# Micromirror_Ampli_PCB.net
KiCad netlist of a schematic drawn in EAGLE
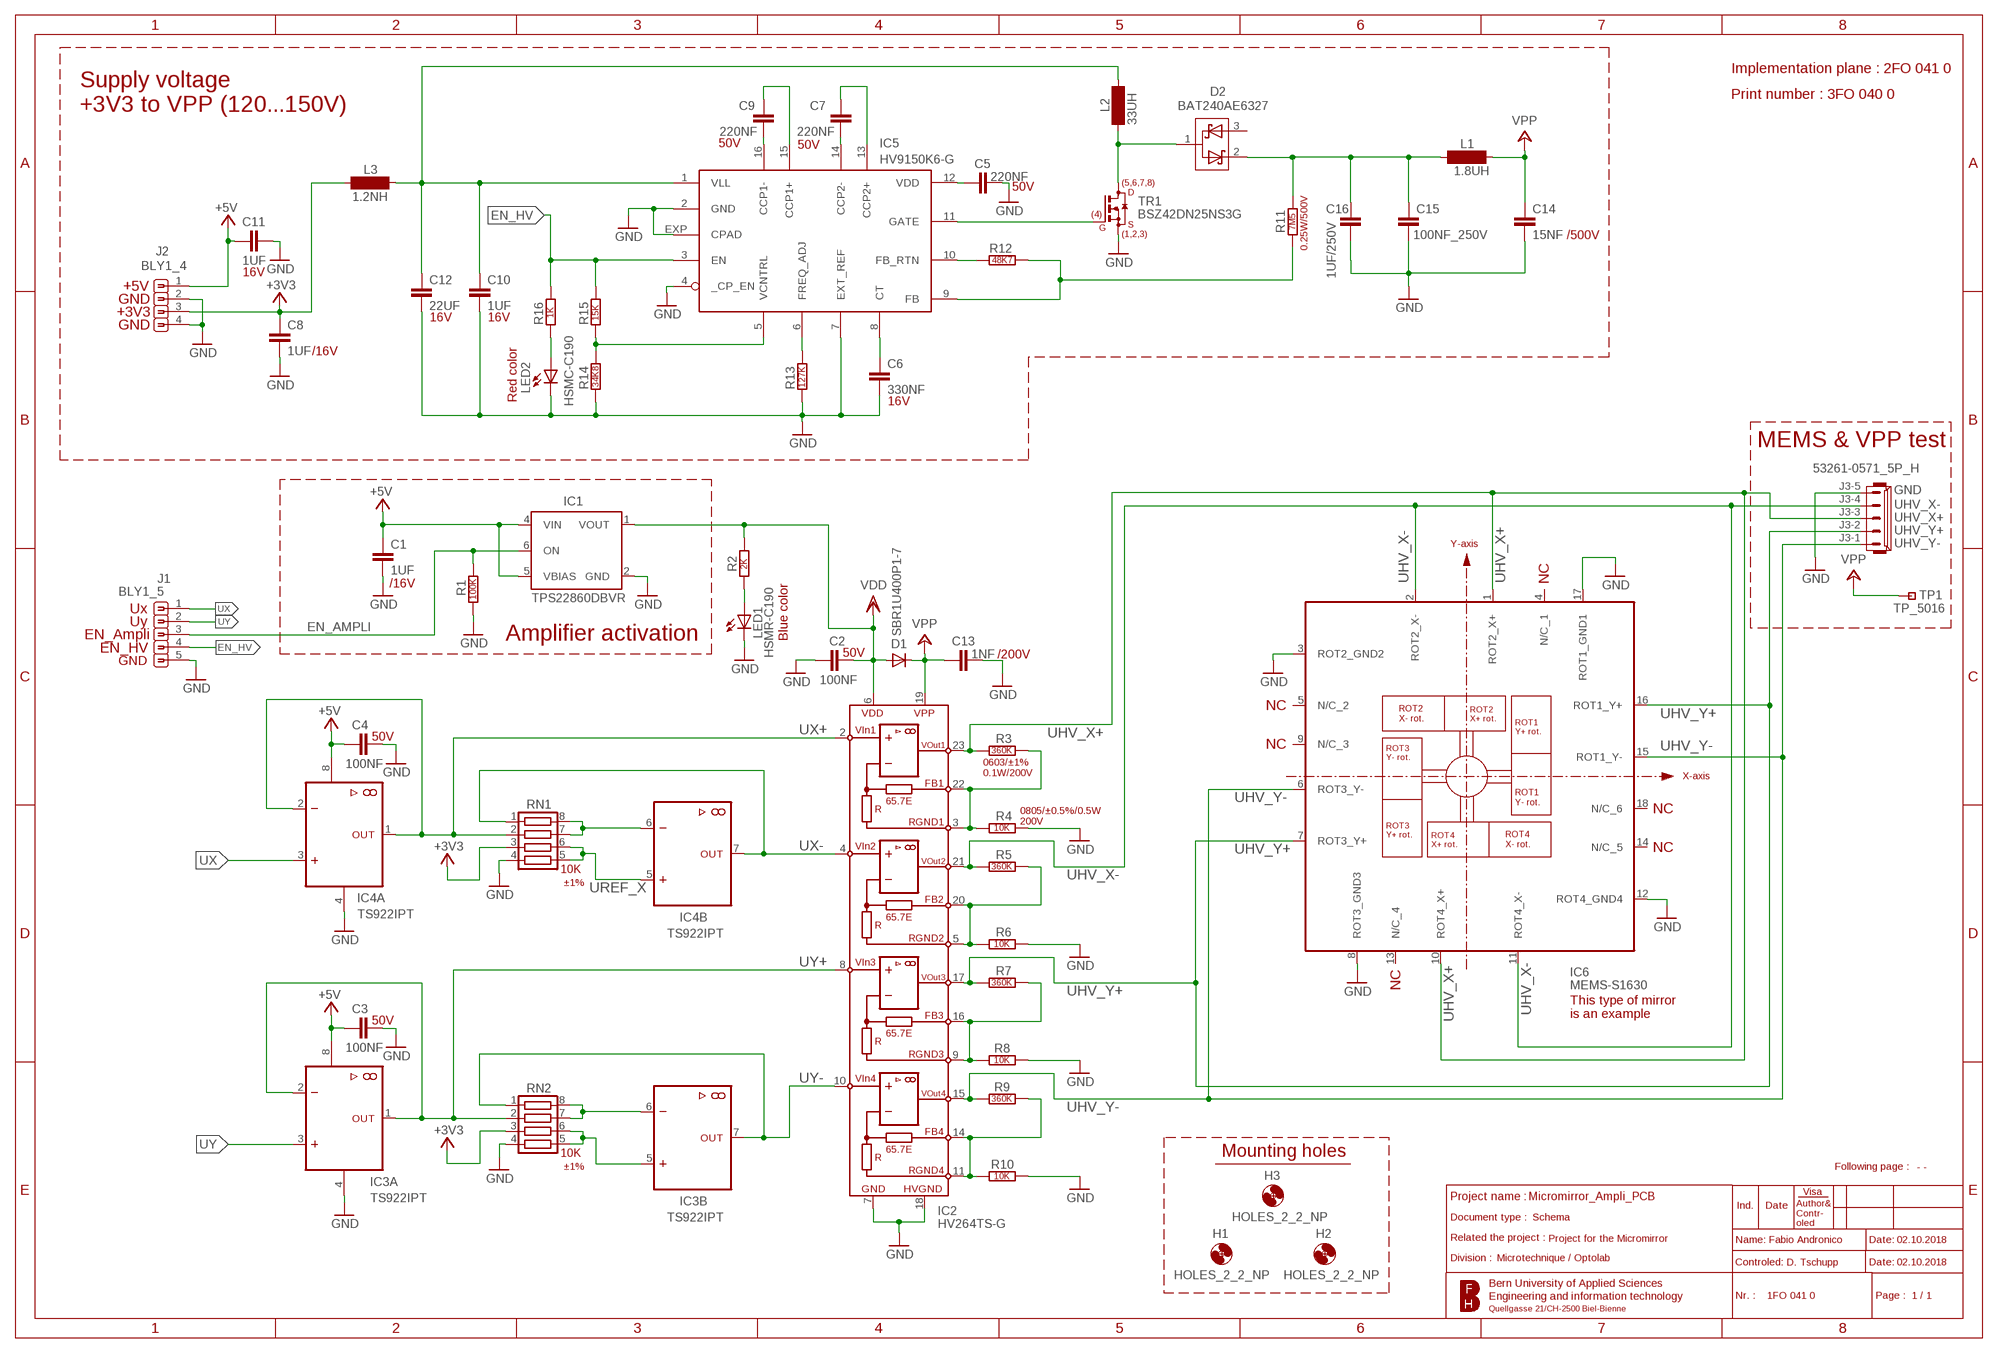
[diagram p0: schematic, sheet 1]

(export (version "E")
  (design (tool "Eeschema 10.0.6"))
  (components
    (comp (ref "C1")
      (value "1UF")
      (footprint "eagle-import:C0603")
      (fields (field (name "MANUFACTURER") "KEMET") (field (name "TOLERANCE") "±5%"))
      (libsource (lib "eagle-import") (part "1UF"))
    )
    (comp (ref "C2")
      (value "100NF")
      (footprint "eagle-import:C0603")
      (fields (field (name "MANUFACTURER") "Kemet") (field (name "TOLERANCE") "±10%"))
      (libsource (lib "eagle-import") (part "100NF"))
    )
    (comp (ref "C3")
      (value "100NF")
      (footprint "eagle-import:C0603")
      (fields (field (name "MANUFACTURER") "Kemet") (field (name "TOLERANCE") "±10%"))
      (libsource (lib "eagle-import") (part "100NF"))
    )
    (comp (ref "C4")
      (value "100NF")
      (footprint "eagle-import:C0603")
      (fields (field (name "MANUFACTURER") "Kemet") (field (name "TOLERANCE") "±10%"))
      (libsource (lib "eagle-import") (part "100NF"))
    )
    (comp (ref "C5")
      (value "220NF")
      (footprint "eagle-import:C0603")
      (fields (field (name "MANUFACTURER") "Murata") (field (name "TOLERANCE") "±10%"))
      (libsource (lib "eagle-import") (part "220NF"))
    )
    (comp (ref "C6")
      (value "330NF")
      (footprint "eagle-import:C0603")
      (fields (field (name "MANUFACTURER") "AVX") (field (name "TOLERANCE") "±10%"))
      (libsource (lib "eagle-import") (part "330NF"))
    )
    (comp (ref "C7")
      (value "220NF")
      (footprint "eagle-import:C0603")
      (fields (field (name "MANUFACTURER") "Murata") (field (name "TOLERANCE") "±10%"))
      (libsource (lib "eagle-import") (part "220NF"))
    )
    (comp (ref "C8")
      (value "1UF")
      (footprint "eagle-import:C0603")
      (fields (field (name "MANUFACTURER") "KEMET") (field (name "TOLERANCE") "±5%"))
      (libsource (lib "eagle-import") (part "1UF"))
    )
    (comp (ref "C9")
      (value "220NF")
      (footprint "eagle-import:C0603")
      (fields (field (name "MANUFACTURER") "Murata") (field (name "TOLERANCE") "±10%"))
      (libsource (lib "eagle-import") (part "220NF"))
    )
    (comp (ref "C10")
      (value "1UF")
      (footprint "eagle-import:C0603")
      (fields (field (name "MANUFACTURER") "KEMET") (field (name "TOLERANCE") "±5%"))
      (libsource (lib "eagle-import") (part "1UF"))
    )
    (comp (ref "C11")
      (value "1UF")
      (footprint "eagle-import:C0603")
      (fields (field (name "MANUFACTURER") "KEMET") (field (name "TOLERANCE") "±5%"))
      (libsource (lib "eagle-import") (part "1UF"))
    )
    (comp (ref "C12")
      (value "22UF")
      (footprint "eagle-import:C0805")
      (fields (field (name "MANUFACTURER") "Murata") (field (name "TOLERANCE") "±20%"))
      (libsource (lib "eagle-import") (part "22UF"))
    )
    (comp (ref "C13")
      (value "1NF")
      (footprint "eagle-import:C0603")
      (fields (field (name "MANUFACTURER") "Kemet") (field (name "TOLERANCE") "±5%"))
      (libsource (lib "eagle-import") (part "1NF"))
    )
    (comp (ref "C14")
      (value "15NF")
      (footprint "eagle-import:C0805")
      (fields (field (name "MANUFACTURER") "Kemet") (field (name "TOLERANCE") "±5%"))
      (libsource (lib "eagle-import") (part "15NF"))
    )
    (comp (ref "C15")
      (value "100NF_250V")
      (footprint "eagle-import:C0805")
      (fields (field (name "MANUFACTURER") "TDK") (field (name "TOLERANCE") "±20%"))
      (libsource (lib "eagle-import") (part "100NF_250V"))
    )
    (comp (ref "C16")
      (value "1UF/250V")
      (footprint "eagle-import:C1812")
      (fields (field (name "MANUFACTURER") "TDK") (field (name "TOLERANCE") "±10%"))
      (libsource (lib "eagle-import") (part "1UF/250V"))
    )
    (comp (ref "D1")
      (value "SBR1U400P1-7")
      (footprint "eagle-import:POWERDI_123")
      (libsource (lib "eagle-import") (part "SBR1U400P1-7"))
    )
    (comp (ref "D2")
      (value "BAT240AE6327")
      (footprint "eagle-import:SOT23-3")
      (fields (field (name "MANUFACTURER") "Infineon"))
      (libsource (lib "eagle-import") (part "BAT240AE6327"))
    )
    (comp (ref "H1")
      (value "HOLES_2_2_NP")
      (footprint "eagle-import:2_2_NP")
      (libsource (lib "eagle-import") (part "HOLES_2_2_NP"))
    )
    (comp (ref "H2")
      (value "HOLES_2_2_NP")
      (footprint "eagle-import:2_2_NP")
      (libsource (lib "eagle-import") (part "HOLES_2_2_NP"))
    )
    (comp (ref "H3")
      (value "HOLES_2_2_NP")
      (footprint "eagle-import:2_2_NP")
      (libsource (lib "eagle-import") (part "HOLES_2_2_NP"))
    )
    (comp (ref "IC1")
      (value "TPS22860DBVR")
      (footprint "eagle-import:SOT23-6")
      (fields (field (name "MANUFACTURER") "Texas Instruments"))
      (libsource (lib "eagle-import") (part "TPS22860DBVR"))
    )
    (comp (ref "IC2")
      (value "HV264TS-G")
      (footprint "eagle-import:TSSOP24")
      (fields (field (name "MANUFACTURER") "Supertex"))
      (libsource (lib "eagle-import") (part "HV264TS-G"))
    )
    (comp (ref "IC3")
      (value "TS922IPT")
      (footprint "eagle-import:TSSOP8")
      (libsource (lib "eagle-import") (part "TS922IPT"))
    )
    (comp (ref "IC4")
      (value "TS922IPT")
      (footprint "eagle-import:TSSOP8")
      (libsource (lib "eagle-import") (part "TS922IPT"))
    )
    (comp (ref "IC5")
      (value "HV9150K6-G")
      (footprint "eagle-import:QFN16")
      (fields (field (name "MANUFACTURER") "Microchip"))
      (libsource (lib "eagle-import") (part "HV9150K6-G"))
    )
    (comp (ref "IC6")
      (value "MEMS-S1630")
      (footprint "eagle-import:LCC18")
      (fields (field (name "MANUFACTURER") "mirrorcletech"))
      (libsource (lib "eagle-import") (part "MEMS-S1630"))
    )
    (comp (ref "J1")
      (value "BLY1_5")
      (footprint "eagle-import:BLY1_5_2MM")
      (fields (field (name "MANUFACTURER") "Fischer Elektronik"))
      (libsource (lib "eagle-import") (part "BLY1_5"))
    )
    (comp (ref "J2")
      (value "BLY1_4")
      (footprint "eagle-import:BLY1_4_2MM")
      (fields (field (name "MANUFACTURER") "Fischer Elektronik"))
      (libsource (lib "eagle-import") (part "BLY1_4"))
    )
    (comp (ref "J3")
      (value "53261-0571_5P_H")
      (footprint "eagle-import:53261-05")
      (fields (field (name "MANUFACTURER") "Molex"))
      (libsource (lib "eagle-import") (part "53261-0571_5P_H"))
    )
    (comp (ref "L1")
      (value "1.8UH")
      (footprint "eagle-import:L0805")
      (fields (field (name "MANUFACTURER") "Laird"))
      (libsource (lib "eagle-import") (part "1.8UH"))
    )
    (comp (ref "L2")
      (value "33UH")
      (footprint "eagle-import:NR5040")
      (fields (field (name "MANUFACTURER") "Taiyo Yuden") (field (name "TOLERANCE") "±20%"))
      (libsource (lib "eagle-import") (part "33UH"))
    )
    (comp (ref "L3")
      (value "1.2NH")
      (footprint "eagle-import:L08051R2CEWTR")
      (fields (field (name "MANUFACTURER") "AVX") (field (name "TOLERANCE") "±16%"))
      (libsource (lib "eagle-import") (part "1.2NH"))
    )
    (comp (ref "LED1")
      (value "HSMR-C190")
      (footprint "eagle-import:CHIP-LED-0603")
      (fields (field (name "MANUFACTURER") "Broadcom Limited"))
      (libsource (lib "eagle-import") (part "HSMR-C190"))
    )
    (comp (ref "LED2")
      (value "HSMC-C190")
      (footprint "eagle-import:CHIP-LED-0603")
      (fields (field (name "MANUFACTURER") "Broadcom Limited"))
      (libsource (lib "eagle-import") (part "HSMC-C190"))
    )
    (comp (ref "R1")
      (value "100K")
      (footprint "eagle-import:R0603")
      (fields
        (field (name "MANUFACTURER") "KOA")
        (field (name "POWER") "0,1W")
        (field (name "TOLERANCE") "±1%")
      )
      (libsource (lib "eagle-import") (part "100K"))
    )
    (comp (ref "R2")
      (value "2K")
      (footprint "eagle-import:R0603")
      (fields
        (field (name "MANUFACTURER") "KOA")
        (field (name "POWER") "0,1W")
        (field (name "TOLERANCE") "±1%")
      )
      (libsource (lib "eagle-import") (part "2K"))
    )
    (comp (ref "R3")
      (value "360K")
      (footprint "eagle-import:R0603")
      (fields
        (field (name "MANUFACTURER") "Multicomp")
        (field (name "POWER") "0,1W")
        (field (name "TOLERANCE") "±1%")
      )
      (libsource (lib "eagle-import") (part "360K"))
    )
    (comp (ref "R4")
      (value "10K_0.5%")
      (footprint "eagle-import:R0805")
      (fields
        (field (name "MANUFACTURER") "KOA")
        (field (name "POWER") "0.5W")
        (field (name "TOLERANCE") "±0.5%")
      )
      (libsource (lib "eagle-import") (part "10K_0.5%"))
    )
    (comp (ref "R5")
      (value "360K")
      (footprint "eagle-import:R0603")
      (fields
        (field (name "MANUFACTURER") "Multicomp")
        (field (name "POWER") "0,1W")
        (field (name "TOLERANCE") "±1%")
      )
      (libsource (lib "eagle-import") (part "360K"))
    )
    (comp (ref "R6")
      (value "10K_0.5%")
      (footprint "eagle-import:R0805")
      (fields
        (field (name "MANUFACTURER") "KOA")
        (field (name "POWER") "0.5W")
        (field (name "TOLERANCE") "±0.5%")
      )
      (libsource (lib "eagle-import") (part "10K_0.5%"))
    )
    (comp (ref "R7")
      (value "360K")
      (footprint "eagle-import:R0603")
      (fields
        (field (name "MANUFACTURER") "Multicomp")
        (field (name "POWER") "0,1W")
        (field (name "TOLERANCE") "±1%")
      )
      (libsource (lib "eagle-import") (part "360K"))
    )
    (comp (ref "R8")
      (value "10K_0.5%")
      (footprint "eagle-import:R0805")
      (fields
        (field (name "MANUFACTURER") "KOA")
        (field (name "POWER") "0.5W")
        (field (name "TOLERANCE") "±0.5%")
      )
      (libsource (lib "eagle-import") (part "10K_0.5%"))
    )
    (comp (ref "R9")
      (value "360K")
      (footprint "eagle-import:R0603")
      (fields
        (field (name "MANUFACTURER") "Multicomp")
        (field (name "POWER") "0,1W")
        (field (name "TOLERANCE") "±1%")
      )
      (libsource (lib "eagle-import") (part "360K"))
    )
    (comp (ref "R10")
      (value "10K_0.5%")
      (footprint "eagle-import:R0805")
      (fields
        (field (name "MANUFACTURER") "KOA")
        (field (name "POWER") "0.5W")
        (field (name "TOLERANCE") "±0.5%")
      )
      (libsource (lib "eagle-import") (part "10K_0.5%"))
    )
    (comp (ref "R11")
      (value "7M5")
      (footprint "eagle-import:R1206")
      (fields
        (field (name "MANUFACTURER") "KOA")
        (field (name "POWER") "0,25W")
        (field (name "TOLERANCE") "±1%")
      )
      (libsource (lib "eagle-import") (part "7M5"))
    )
    (comp (ref "R12")
      (value "48K7")
      (footprint "eagle-import:R0603")
      (fields
        (field (name "MANUFACTURER") "Panasonic")
        (field (name "POWER") "0,1W")
        (field (name "TOLERANCE") "±1%")
      )
      (libsource (lib "eagle-import") (part "48K7"))
    )
    (comp (ref "R13")
      (value "127K")
      (footprint "eagle-import:R0603")
      (fields
        (field (name "MANUFACTURER") "Yageo")
        (field (name "POWER") "0,1W")
        (field (name "TOLERANCE") "±1%")
      )
      (libsource (lib "eagle-import") (part "127K"))
    )
    (comp (ref "R14")
      (value "34K8")
      (footprint "eagle-import:R0603")
      (fields
        (field (name "MANUFACTURER") "Panasonic")
        (field (name "POWER") "0,1W")
        (field (name "TOLERANCE") "±1%")
      )
      (libsource (lib "eagle-import") (part "34K8"))
    )
    (comp (ref "R15")
      (value "15K")
      (footprint "eagle-import:R0603")
      (fields
        (field (name "MANUFACTURER") "Panasonic")
        (field (name "POWER") "0,2W")
        (field (name "TOLERANCE") "±0.1%")
      )
      (libsource (lib "eagle-import") (part "15K"))
    )
    (comp (ref "R16")
      (value "1K_0.1W")
      (footprint "eagle-import:R0603")
      (fields
        (field (name "MANUFACTURER") "KOA")
        (field (name "POWER") "0,1W")
        (field (name "TOLERANCE") "±1%")
      )
      (libsource (lib "eagle-import") (part "1K_0.1W"))
    )
    (comp (ref "RN1")
      (value "10K")
      (footprint "eagle-import:RN1206")
      (fields (field (name "MANUFACTURER") "Bourns") (field (name "TOLERANCE") "±1%"))
      (libsource (lib "eagle-import") (part "10K"))
    )
    (comp (ref "RN2")
      (value "10K")
      (footprint "eagle-import:RN1206")
      (fields (field (name "MANUFACTURER") "Bourns") (field (name "TOLERANCE") "±1%"))
      (libsource (lib "eagle-import") (part "10K"))
    )
    (comp (ref "TP1")
      (value "TP_5016")
      (footprint "eagle-import:5016")
      (libsource (lib "eagle-import") (part "5016"))
    )
    (comp (ref "TR1")
      (value "BSZ42DN25NS3G")
      (footprint "eagle-import:TSDSON-8")
      (fields (field (name "MANUFACTURER") "Infineon"))
      (libsource (lib "eagle-import") (part "BSZ42DN25NS3G"))
    )
  )
  (nets
    (net (code "1") (name "+3V3") (class "Default")
      (node (ref "C8") (pin "1") (pinfunction "1_1") (pintype "passive"))
      (node (ref "J2") (pin "3") (pinfunction "3_3") (pintype "passive"))
      (node (ref "L3") (pin "1") (pinfunction "1_1") (pintype "passive"))
      (node (ref "RN1") (pin "3") (pinfunction "3_3") (pintype "passive"))
      (node (ref "RN2") (pin "3") (pinfunction "3_3") (pintype "passive"))
    )
    (net (code "2") (name "+5V") (class "Default")
      (node (ref "C1") (pin "1") (pinfunction "1_1") (pintype "passive"))
      (node (ref "C11") (pin "1") (pinfunction "1_1") (pintype "passive"))
      (node (ref "C3") (pin "1") (pinfunction "1_1") (pintype "passive"))
      (node (ref "C4") (pin "1") (pinfunction "1_1") (pintype "passive"))
      (node (ref "IC1") (pin "4") (pinfunction "VIN_4") (pintype "input"))
      (node (ref "IC1") (pin "5") (pinfunction "VBIAS_5") (pintype "input"))
      (node (ref "IC3") (pin "8") (pinfunction "+5V_8") (pintype "power_in"))
      (node (ref "IC4") (pin "8") (pinfunction "+5V_8") (pintype "power_in"))
      (node (ref "J2") (pin "1") (pinfunction "1_1") (pintype "passive"))
    )
    (net (code "3") (name "/EN_AMPLI") (class "Default")
      (node (ref "IC1") (pin "6") (pinfunction "ON_6") (pintype "input"))
      (node (ref "J1") (pin "3") (pinfunction "3_3") (pintype "passive"))
      (node (ref "R1") (pin "1") (pinfunction "1_1") (pintype "passive"))
    )
    (net (code "4") (name "/UHV_X+") (class "Default")
      (node (ref "IC2") (pin "23") (pinfunction "VOUT1_23") (pintype "output"))
      (node (ref "IC6") (pin "1") (pinfunction "ROT2_X+_1") (pintype "input"))
      (node (ref "IC6") (pin "10") (pinfunction "ROT4_X+_10") (pintype "input"))
      (node (ref "J3") (pin "3") (pinfunction "S_3") (pintype "passive"))
      (node (ref "R3") (pin "1") (pinfunction "1_1") (pintype "passive"))
    )
    (net (code "5") (name "/UHV_X-") (class "Default")
      (node (ref "IC2") (pin "21") (pinfunction "VOUT2_21") (pintype "output"))
      (node (ref "IC6") (pin "11") (pinfunction "ROT4_X-_11") (pintype "input"))
      (node (ref "IC6") (pin "2") (pinfunction "ROT2_X-_2") (pintype "input"))
      (node (ref "J3") (pin "4") (pinfunction "S_4") (pintype "passive"))
      (node (ref "R5") (pin "1") (pinfunction "1_1") (pintype "passive"))
    )
    (net (code "6") (name "/UHV_Y+") (class "Default")
      (node (ref "IC2") (pin "17") (pinfunction "VOUT3_17") (pintype "output"))
      (node (ref "IC6") (pin "16") (pinfunction "ROT1_Y+_16") (pintype "input"))
      (node (ref "IC6") (pin "7") (pinfunction "ROT3_Y+_7") (pintype "input"))
      (node (ref "J3") (pin "2") (pinfunction "S_2") (pintype "passive"))
      (node (ref "R7") (pin "1") (pinfunction "1_1") (pintype "passive"))
    )
    (net (code "7") (name "/UHV_Y-") (class "Default")
      (node (ref "IC2") (pin "15") (pinfunction "VOUT4_15") (pintype "output"))
      (node (ref "IC6") (pin "15") (pinfunction "ROT1_Y-_15") (pintype "input"))
      (node (ref "IC6") (pin "6") (pinfunction "ROT3_Y-_6") (pintype "input"))
      (node (ref "J3") (pin "1") (pinfunction "S_1") (pintype "passive"))
      (node (ref "R9") (pin "1") (pinfunction "1_1") (pintype "passive"))
    )
    (net (code "8") (name "/UREF_X") (class "Default")
      (node (ref "IC4") (pin "5") (pinfunction "+IN_5") (pintype "input"))
      (node (ref "RN1") (pin "5") (pinfunction "5_5") (pintype "passive"))
      (node (ref "RN1") (pin "6") (pinfunction "6_6") (pintype "passive"))
    )
    (net (code "9") (name "/UX+") (class "Default")
      (node (ref "IC2") (pin "2") (pinfunction "+VIN1_2") (pintype "input"))
      (node (ref "IC4") (pin "1") (pinfunction "OUT_1") (pintype "output"))
      (node (ref "IC4") (pin "2") (pinfunction "-IN_2") (pintype "input"))
      (node (ref "RN1") (pin "2") (pinfunction "2_2") (pintype "passive"))
    )
    (net (code "10") (name "/UX-") (class "Default")
      (node (ref "IC2") (pin "4") (pinfunction "+VIN2_4") (pintype "input"))
      (node (ref "IC4") (pin "7") (pinfunction "OUT_7") (pintype "output"))
      (node (ref "RN1") (pin "1") (pinfunction "1_1") (pintype "passive"))
    )
    (net (code "11") (name "/UY+") (class "Default")
      (node (ref "IC2") (pin "8") (pinfunction "+VIN3_8") (pintype "input"))
      (node (ref "IC3") (pin "1") (pinfunction "OUT_1") (pintype "output"))
      (node (ref "IC3") (pin "2") (pinfunction "-IN_2") (pintype "input"))
      (node (ref "RN2") (pin "2") (pinfunction "2_2") (pintype "passive"))
    )
    (net (code "12") (name "/UY-") (class "Default")
      (node (ref "IC2") (pin "10") (pinfunction "+VIN4_10") (pintype "input"))
      (node (ref "IC3") (pin "7") (pinfunction "OUT_7") (pintype "output"))
      (node (ref "RN2") (pin "1") (pinfunction "1_1") (pintype "passive"))
    )
    (net (code "13") (name "EN_HV") (class "Default")
      (node (ref "IC5") (pin "3") (pinfunction "EN_3") (pintype "bidirectional"))
      (node (ref "J1") (pin "4") (pinfunction "4_4") (pintype "passive"))
      (node (ref "R15") (pin "2") (pinfunction "2_2") (pintype "passive"))
      (node (ref "R16") (pin "2") (pinfunction "2_2") (pintype "passive"))
    )
    (net (code "14") (name "GND") (class "Default")
      (node (ref "C1") (pin "2") (pinfunction "2_2") (pintype "passive"))
      (node (ref "C10") (pin "2") (pinfunction "2_2") (pintype "passive"))
      (node (ref "C11") (pin "2") (pinfunction "2_2") (pintype "passive"))
      (node (ref "C12") (pin "2") (pinfunction "2_2") (pintype "passive"))
      (node (ref "C13") (pin "2") (pinfunction "2_2") (pintype "passive"))
      (node (ref "C14") (pin "2") (pinfunction "2_2") (pintype "passive"))
      (node (ref "C15") (pin "2") (pinfunction "2_2") (pintype "passive"))
      (node (ref "C16") (pin "2") (pinfunction "2_2") (pintype "passive"))
      (node (ref "C2") (pin "2") (pinfunction "2_2") (pintype "passive"))
      (node (ref "C3") (pin "2") (pinfunction "2_2") (pintype "passive"))
      (node (ref "C4") (pin "2") (pinfunction "2_2") (pintype "passive"))
      (node (ref "C5") (pin "1") (pinfunction "1_1") (pintype "passive"))
      (node (ref "C6") (pin "2") (pinfunction "2_2") (pintype "passive"))
      (node (ref "C8") (pin "2") (pinfunction "2_2") (pintype "passive"))
      (node (ref "IC1") (pin "2") (pinfunction "GND_2") (pintype "power_in"))
      (node (ref "IC2") (pin "18") (pinfunction "HVGND_18") (pintype "passive"))
      (node (ref "IC2") (pin "7") (pinfunction "GND_7") (pintype "power_in"))
      (node (ref "IC3") (pin "4") (pinfunction "GND_4") (pintype "power_in"))
      (node (ref "IC4") (pin "4") (pinfunction "GND_4") (pintype "power_in"))
      (node (ref "IC5") (pin "2") (pinfunction "GND_2") (pintype "power_in"))
      (node (ref "IC5") (pin "4") (pinfunction "_CP_EN_4") (pintype "bidirectional"))
      (node (ref "IC5") (pin "7") (pinfunction "EXT_REF_7") (pintype "bidirectional"))
      (node (ref "IC5") (pin "EXP") (pinfunction "CPAD_EXP") (pintype "passive"))
      (node (ref "IC6") (pin "12") (pinfunction "ROT4_GND4_12") (pintype "passive"))
      (node (ref "IC6") (pin "17") (pinfunction "ROT1_GND1_17") (pintype "passive"))
      (node (ref "IC6") (pin "3") (pinfunction "ROT2_GND2_3") (pintype "passive"))
      (node (ref "IC6") (pin "8") (pinfunction "ROT3_GND3_8") (pintype "passive"))
      (node (ref "J1") (pin "5") (pinfunction "5_5") (pintype "passive"))
      (node (ref "J2") (pin "2") (pinfunction "2_2") (pintype "passive"))
      (node (ref "J2") (pin "4") (pinfunction "4_4") (pintype "passive"))
      (node (ref "J3") (pin "5") (pinfunction "S_5") (pintype "passive"))
      (node (ref "LED1") (pin "C") (pinfunction "C_C") (pintype "passive"))
      (node (ref "LED2") (pin "C") (pinfunction "C_C") (pintype "passive"))
      (node (ref "R1") (pin "2") (pinfunction "2_2") (pintype "passive"))
      (node (ref "R10") (pin "2") (pinfunction "2_2") (pintype "passive"))
      (node (ref "R13") (pin "1") (pinfunction "1_1") (pintype "passive"))
      (node (ref "R14") (pin "1") (pinfunction "1_1") (pintype "passive"))
      (node (ref "R4") (pin "2") (pinfunction "2_2") (pintype "passive"))
      (node (ref "R6") (pin "2") (pinfunction "2_2") (pintype "passive"))
      (node (ref "R8") (pin "2") (pinfunction "2_2") (pintype "passive"))
      (node (ref "RN1") (pin "4") (pinfunction "4_4") (pintype "passive"))
      (node (ref "RN2") (pin "4") (pinfunction "4_4") (pintype "passive"))
      (node (ref "TR1") (pin "1") (pinfunction "S_1") (pintype "passive"))
      (node (ref "TR1") (pin "2") (pinfunction "S_2") (pintype "passive"))
      (node (ref "TR1") (pin "3") (pinfunction "S_3") (pintype "passive"))
    )
    (net (code "15") (name "Net-(C15-Pad1)") (class "Default")
      (node (ref "C15") (pin "1") (pinfunction "1_1") (pintype "passive"))
      (node (ref "C16") (pin "1") (pinfunction "1_1") (pintype "passive"))
      (node (ref "D2") (pin "2") (pinfunction "2_2") (pintype "passive"))
      (node (ref "L1") (pin "1") (pinfunction "1_1") (pintype "passive"))
      (node (ref "R11") (pin "2") (pinfunction "2_2") (pintype "passive"))
    )
    (net (code "16") (name "Net-(IC2A-FB1)") (class "Default")
      (node (ref "IC2") (pin "22") (pinfunction "FB1_22") (pintype "bidirectional"))
      (node (ref "IC2") (pin "3") (pinfunction "RGND1_3") (pintype "bidirectional"))
      (node (ref "R3") (pin "2") (pinfunction "2_2") (pintype "passive"))
      (node (ref "R4") (pin "1") (pinfunction "1_1") (pintype "passive"))
    )
    (net (code "17") (name "Net-(IC2A-FB2)") (class "Default")
      (node (ref "IC2") (pin "20") (pinfunction "FB2_20") (pintype "bidirectional"))
      (node (ref "IC2") (pin "5") (pinfunction "RGND2_5") (pintype "bidirectional"))
      (node (ref "R5") (pin "2") (pinfunction "2_2") (pintype "passive"))
      (node (ref "R6") (pin "1") (pinfunction "1_1") (pintype "passive"))
    )
    (net (code "18") (name "Net-(IC2A-FB3)") (class "Default")
      (node (ref "IC2") (pin "16") (pinfunction "FB3_16") (pintype "bidirectional"))
      (node (ref "IC2") (pin "9") (pinfunction "RGND3_9") (pintype "bidirectional"))
      (node (ref "R7") (pin "2") (pinfunction "2_2") (pintype "passive"))
      (node (ref "R8") (pin "1") (pinfunction "1_1") (pintype "passive"))
    )
    (net (code "19") (name "Net-(IC2A-FB4)") (class "Default")
      (node (ref "IC2") (pin "11") (pinfunction "RGND4_11") (pintype "bidirectional"))
      (node (ref "IC2") (pin "14") (pinfunction "FB4_14") (pintype "bidirectional"))
      (node (ref "R10") (pin "1") (pinfunction "1_1") (pintype "passive"))
      (node (ref "R9") (pin "2") (pinfunction "2_2") (pintype "passive"))
    )
    (net (code "20") (name "Net-(IC3B-+IN)") (class "Default")
      (node (ref "IC3") (pin "5") (pinfunction "+IN_5") (pintype "input"))
      (node (ref "RN2") (pin "5") (pinfunction "5_5") (pintype "passive"))
      (node (ref "RN2") (pin "6") (pinfunction "6_6") (pintype "passive"))
    )
    (net (code "21") (name "Net-(IC3B--IN)") (class "Default")
      (node (ref "IC3") (pin "6") (pinfunction "-IN_6") (pintype "input"))
      (node (ref "RN2") (pin "7") (pinfunction "7_7") (pintype "passive"))
      (node (ref "RN2") (pin "8") (pinfunction "8_8") (pintype "passive"))
    )
    (net (code "22") (name "Net-(IC4B--IN)") (class "Default")
      (node (ref "IC4") (pin "6") (pinfunction "-IN_6") (pintype "input"))
      (node (ref "RN1") (pin "7") (pinfunction "7_7") (pintype "passive"))
      (node (ref "RN1") (pin "8") (pinfunction "8_8") (pintype "passive"))
    )
    (net (code "23") (name "Net-(IC5-CCP1+)") (class "Default")
      (node (ref "C9") (pin "2") (pinfunction "2_2") (pintype "passive"))
      (node (ref "IC5") (pin "15") (pinfunction "CCP1+_15") (pintype "passive"))
    )
    (net (code "24") (name "Net-(IC5-CCP1-)") (class "Default")
      (node (ref "C9") (pin "1") (pinfunction "1_1") (pintype "passive"))
      (node (ref "IC5") (pin "16") (pinfunction "CCP1-_16") (pintype "passive"))
    )
    (net (code "25") (name "Net-(IC5-CCP2+)") (class "Default")
      (node (ref "C7") (pin "1") (pinfunction "1_1") (pintype "passive"))
      (node (ref "IC5") (pin "13") (pinfunction "CCP2+_13") (pintype "passive"))
    )
    (net (code "26") (name "Net-(IC5-CCP2-)") (class "Default")
      (node (ref "C7") (pin "2") (pinfunction "2_2") (pintype "passive"))
      (node (ref "IC5") (pin "14") (pinfunction "CCP2-_14") (pintype "passive"))
    )
    (net (code "27") (name "Net-(IC5-CT)") (class "Default")
      (node (ref "C6") (pin "1") (pinfunction "1_1") (pintype "passive"))
      (node (ref "IC5") (pin "8") (pinfunction "CT_8") (pintype "passive"))
    )
    (net (code "28") (name "Net-(IC5-FB)") (class "Default")
      (node (ref "IC5") (pin "9") (pinfunction "FB_9") (pintype "bidirectional"))
      (node (ref "R11") (pin "1") (pinfunction "1_1") (pintype "passive"))
      (node (ref "R12") (pin "2") (pinfunction "2_2") (pintype "passive"))
    )
    (net (code "29") (name "Net-(IC5-FB_RTN)") (class "Default")
      (node (ref "IC5") (pin "10") (pinfunction "FB_RTN_10") (pintype "bidirectional"))
      (node (ref "R12") (pin "1") (pinfunction "1_1") (pintype "passive"))
    )
    (net (code "30") (name "Net-(IC5-FREQ_ADJ)") (class "Default")
      (node (ref "IC5") (pin "6") (pinfunction "FREQ_ADJ_6") (pintype "bidirectional"))
      (node (ref "R13") (pin "2") (pinfunction "2_2") (pintype "passive"))
    )
    (net (code "31") (name "Net-(IC5-GATE)") (class "Default")
      (node (ref "IC5") (pin "11") (pinfunction "GATE_11") (pintype "bidirectional"))
      (node (ref "TR1") (pin "4") (pinfunction "G_4") (pintype "passive"))
    )
    (net (code "32") (name "Net-(IC5-VCNTRL)") (class "Default")
      (node (ref "IC5") (pin "5") (pinfunction "VCNTRL_5") (pintype "bidirectional"))
      (node (ref "R14") (pin "2") (pinfunction "2_2") (pintype "passive"))
      (node (ref "R15") (pin "1") (pinfunction "1_1") (pintype "passive"))
    )
    (net (code "33") (name "Net-(IC5-VDD)") (class "Default")
      (node (ref "C5") (pin "2") (pinfunction "2_2") (pintype "passive"))
      (node (ref "IC5") (pin "12") (pinfunction "VDD_12") (pintype "passive"))
    )
    (net (code "34") (name "Net-(IC5-VLL)") (class "Default")
      (node (ref "C10") (pin "1") (pinfunction "1_1") (pintype "passive"))
      (node (ref "C12") (pin "1") (pinfunction "1_1") (pintype "passive"))
      (node (ref "IC5") (pin "1") (pinfunction "VLL_1") (pintype "passive"))
      (node (ref "L2") (pin "2") (pinfunction "2_2") (pintype "passive"))
      (node (ref "L3") (pin "2") (pinfunction "2_2") (pintype "passive"))
    )
    (net (code "35") (name "Net-(LED1-PadA)") (class "Default")
      (node (ref "LED1") (pin "A") (pinfunction "A_A") (pintype "passive"))
      (node (ref "R2") (pin "1") (pinfunction "1_1") (pintype "passive"))
    )
    (net (code "36") (name "Net-(LED2-PadA)") (class "Default")
      (node (ref "LED2") (pin "A") (pinfunction "A_A") (pintype "passive"))
      (node (ref "R16") (pin "1") (pinfunction "1_1") (pintype "passive"))
    )
    (net (code "37") (name "Net-(TR1-D)") (class "Default")
      (node (ref "D2") (pin "1") (pinfunction "1_1") (pintype "passive"))
      (node (ref "L2") (pin "1") (pinfunction "1_1") (pintype "passive"))
      (node (ref "TR1") (pin "5") (pinfunction "D_5") (pintype "passive"))
    )
    (net (code "38") (name "UX") (class "Default")
      (node (ref "IC4") (pin "3") (pinfunction "+IN_3") (pintype "input"))
      (node (ref "J1") (pin "1") (pinfunction "1_1") (pintype "passive"))
    )
    (net (code "39") (name "UY") (class "Default")
      (node (ref "IC3") (pin "3") (pinfunction "+IN_3") (pintype "input"))
      (node (ref "J1") (pin "2") (pinfunction "2_2") (pintype "passive"))
    )
    (net (code "40") (name "VDD") (class "Default")
      (node (ref "C2") (pin "1") (pinfunction "1_1") (pintype "passive"))
      (node (ref "D1") (pin "A") (pinfunction "A_A") (pintype "passive"))
      (node (ref "IC1") (pin "1") (pinfunction "VOUT_1") (pintype "passive"))
      (node (ref "IC2") (pin "6") (pinfunction "VDD_6") (pintype "power_in"))
      (node (ref "R2") (pin "2") (pinfunction "2_2") (pintype "passive"))
    )
    (net (code "41") (name "VPP") (class "Default")
      (node (ref "C13") (pin "1") (pinfunction "1_1") (pintype "passive"))
      (node (ref "C14") (pin "1") (pinfunction "1_1") (pintype "passive"))
      (node (ref "D1") (pin "C") (pinfunction "C_C") (pintype "passive"))
      (node (ref "IC2") (pin "19") (pinfunction "VPP_19") (pintype "power_in"))
      (node (ref "L1") (pin "2") (pinfunction "2_2") (pintype "passive"))
      (node (ref "TP1") (pin "1") (pinfunction "P_1") (pintype "passive"))
    )
    (net (code "42") (name "unconnected-(D2-Pad3)") (class "Default")
      (node (ref "D2") (pin "3") (pinfunction "3_3") (pintype "passive"))
    )
    (net (code "43") (name "unconnected-(IC6-N{slash}C_1-Pad4)") (class "Default")
      (node (ref "IC6") (pin "4") (pinfunction "N/C_1_4") (pintype "no_connect"))
    )
    (net (code "44") (name "unconnected-(IC6-N{slash}C_2-Pad5)") (class "Default")
      (node (ref "IC6") (pin "5") (pinfunction "N/C_2_5") (pintype "no_connect"))
    )
    (net (code "45") (name "unconnected-(IC6-N{slash}C_3-Pad9)") (class "Default")
      (node (ref "IC6") (pin "9") (pinfunction "N/C_3_9") (pintype "no_connect"))
    )
    (net (code "46") (name "unconnected-(IC6-N{slash}C_4-Pad13)") (class "Default")
      (node (ref "IC6") (pin "13") (pinfunction "N/C_4_13") (pintype "no_connect"))
    )
    (net (code "47") (name "unconnected-(IC6-N{slash}C_5-Pad14)") (class "Default")
      (node (ref "IC6") (pin "14") (pinfunction "N/C_5_14") (pintype "no_connect"))
    )
    (net (code "48") (name "unconnected-(IC6-N{slash}C_6-Pad18)") (class "Default")
      (node (ref "IC6") (pin "18") (pinfunction "N/C_6_18") (pintype "no_connect"))
    )
  )
)
